# MCU.net
KiCad netlist of a schematic drawn in Altium Designer
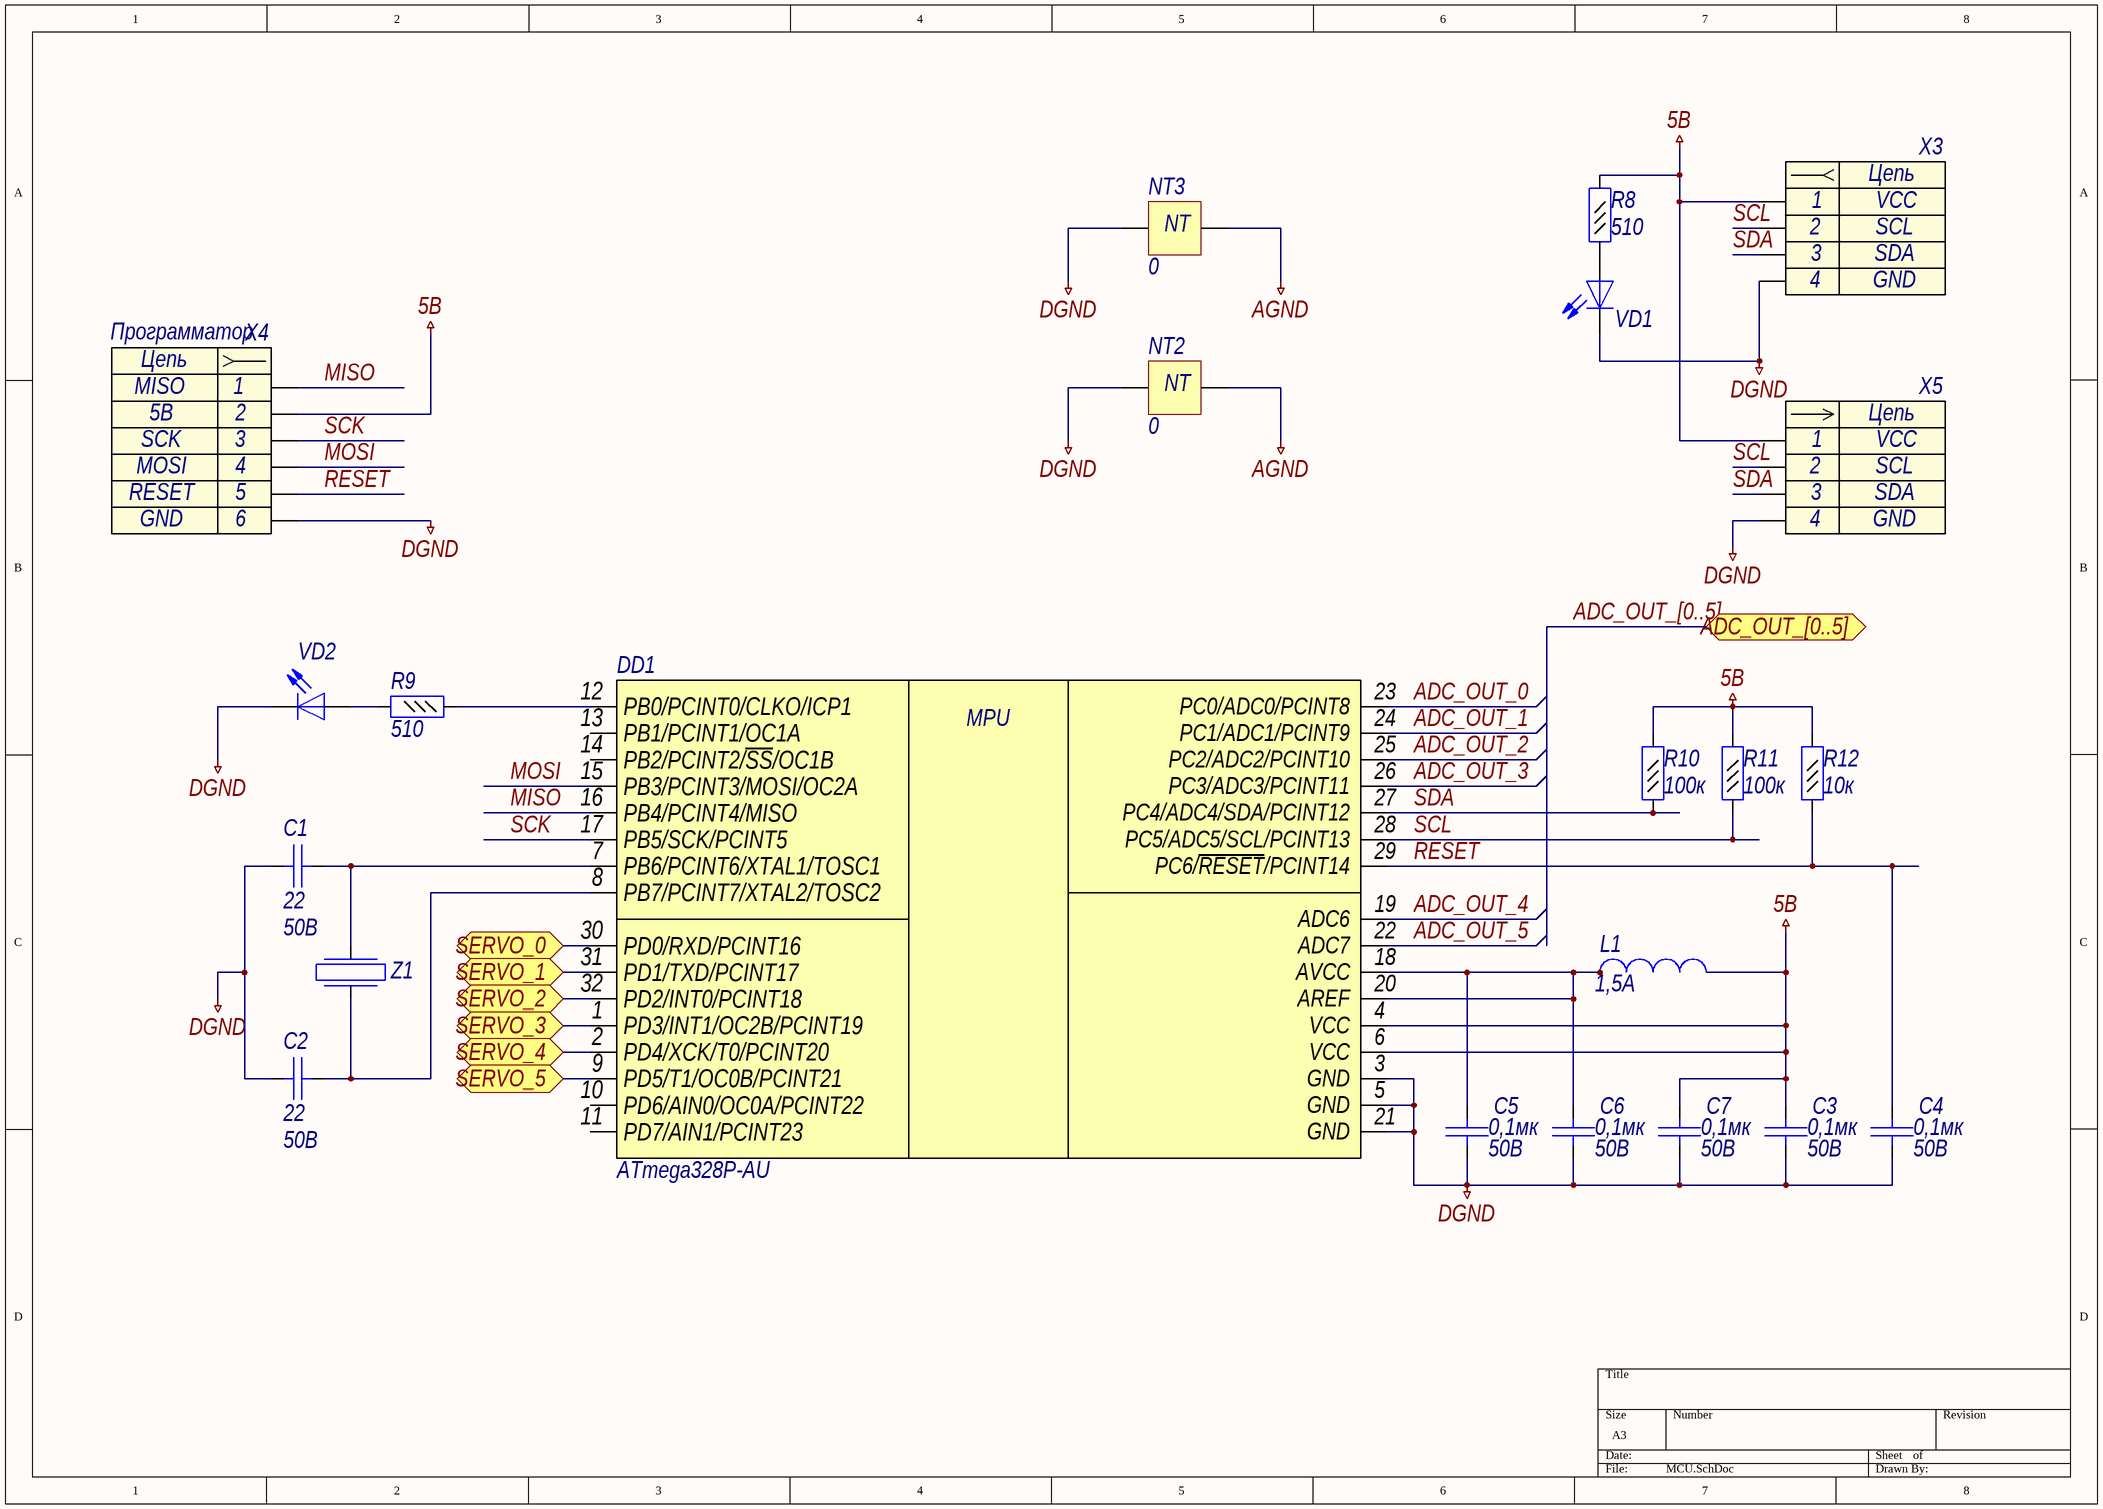
[diagram p0: MCU.SchDoc]

(export (version "E")
  (design (tool "Eeschema 10.0.6"))
  (components
    (comp (ref "C1")
      (value "22")
      (footprint "C0603")
      (description "Конденсатор")
      (fields (field (name "VOLTAGE") "50B") (field (name "PART NUMBER") "CC0603JRNPO9BN220"))
      (libsource (lib "MOP44") (part "Capacitor"))
    )
    (comp (ref "C2")
      (value "22")
      (footprint "C0603")
      (description "Конденсатор")
      (fields (field (name "VOLTAGE") "50B") (field (name "PART NUMBER") "CC0603JRNPO9BN220"))
      (libsource (lib "MOP44") (part "Capacitor"))
    )
    (comp (ref "C3")
      (value "0,1мк")
      (footprint "C0603")
      (description "Конденсатор")
      (fields (field (name "VOLTAGE") "50B") (field (name "PART NUMBER") "GRM188R71H104KA93D"))
      (libsource (lib "MOP44") (part "Capacitor"))
    )
    (comp (ref "C4")
      (value "0,1мк")
      (footprint "C0603")
      (description "Конденсатор")
      (fields (field (name "VOLTAGE") "50B") (field (name "PART NUMBER") "GRM188R71H104KA93D"))
      (libsource (lib "MOP44") (part "Capacitor"))
    )
    (comp (ref "C5")
      (value "0,1мк")
      (footprint "C0603")
      (description "Конденсатор")
      (fields (field (name "VOLTAGE") "50B") (field (name "PART NUMBER") "GRM188R71H104KA93D"))
      (libsource (lib "MOP44") (part "Capacitor"))
    )
    (comp (ref "C6")
      (value "0,1мк")
      (footprint "C0603")
      (description "Конденсатор")
      (fields (field (name "VOLTAGE") "50B") (field (name "PART NUMBER") "GRM188R71H104KA93D"))
      (libsource (lib "MOP44") (part "Capacitor"))
    )
    (comp (ref "C7")
      (value "0,1мк")
      (footprint "C0603")
      (description "Конденсатор")
      (fields (field (name "VOLTAGE") "50B") (field (name "PART NUMBER") "GRM188R71H104KA93D"))
      (libsource (lib "MOP44") (part "Capacitor"))
    )
    (comp (ref "DD1")
      (value "ATmega328P-AU")
      (footprint "TQFP-32")
      (description "Микроконтроллер 8-Бит, picoPower, AVR, 20МГц, 32КБ Flash")
      (fields (field (name "PART NUMBER") "ATmega328P-AU"))
      (libsource (lib "MOP44") (part "ATmega328P-AU"))
    )
    (comp (ref "L1")
      (value "Inductor")
      (footprint "L0603")
      (description "EMI Suppression Filter")
      (fields (field (name "RATED CURRENT") "1,5A") (field (name "PART NUMBER") "BLM18PG181SN1D"))
      (libsource (lib "MOP44") (part "Inductor"))
    )
    (comp (ref "NT2")
      (value "0")
      (footprint "Pofigistor0603")
      (fields (field (name "Comment") "Pofigistor"))
      (libsource (lib "MOP44") (part "Pofigistor"))
    )
    (comp (ref "NT3")
      (value "0")
      (footprint "Pofigistor0603")
      (fields (field (name "Comment") "Pofigistor"))
      (libsource (lib "MOP44") (part "Pofigistor"))
    )
    (comp (ref "R8")
      (value "510")
      (footprint "R0603")
      (description "Резистор")
      (fields (field (name "PART NUMBER") "RC0603FR-07510RL") (field (name "POWER") "0,062Вт"))
      (libsource (lib "") (part "Resistor_0,062Вт_1"))
    )
    (comp (ref "R9")
      (value "510")
      (footprint "R0603")
      (description "Резистор")
      (fields (field (name "PART NUMBER") "RC0603FR-07510RL") (field (name "POWER") "0,062Вт"))
      (libsource (lib "MOP44") (part "Resistor_0,062Вт"))
    )
    (comp (ref "R10")
      (value "100к")
      (footprint "R0603")
      (description "Резистор")
      (fields (field (name "PART NUMBER") "RC0603FR-07100KL") (field (name "POWER") "0,062Вт"))
      (libsource (lib "") (part "Resistor_0,062Вт_1"))
    )
    (comp (ref "R11")
      (value "100к")
      (footprint "R0603")
      (description "Резистор")
      (fields (field (name "PART NUMBER") "RC0603FR-07100KL") (field (name "POWER") "0,062Вт"))
      (libsource (lib "") (part "Resistor_0,062Вт_1"))
    )
    (comp (ref "R12")
      (value "10к")
      (footprint "R0603")
      (description "Резистор")
      (fields (field (name "PART NUMBER") "RC0603FR-0710KL") (field (name "POWER") "0,062Вт"))
      (libsource (lib "") (part "Resistor_0,062Вт_1"))
    )
    (comp (ref "VD1")
      (value "LED")
      (footprint "L_0805")
      (description "Светодиод")
      (fields (field (name "PART NUMBER") "KP-2012EC"))
      (libsource (lib "MOP44") (part "LED"))
    )
    (comp (ref "VD2")
      (value "LED")
      (footprint "L_0805")
      (description "Светодиод")
      (fields (field (name "PART NUMBER") "KP-2012EC"))
      (libsource (lib "MOP44") (part "LED"))
    )
    (comp (ref "X3")
      (value "Header_4_sct")
      (footprint "RJ11_4P4C_V")
      (description "Разъем - 4 конт. розетка")
      (libsource (lib "MOP44") (part "Header_4_sct"))
    )
    (comp (ref "X4")
      (value "Программатор")
      (footprint "PLS2-6")
      (description "Разъем - 6 конт. розетка")
      (libsource (lib "MOP44") (part "Header_6_sct"))
    )
    (comp (ref "X5")
      (value "Header_4_plg")
      (footprint "PLS-4")
      (description "Разъем - 4 конт. вилка")
      (fields (field (name "PART NUMBER") "DS1021-1*4SF112-B"))
      (libsource (lib "MOP44") (part "Header_4_plg"))
    )
    (comp (ref "Z1")
      (value "Crystal")
      (footprint "HC-49SM")
      (description "Кварцевый резонатор")
      (fields (field (name "PART NUMBER") "16.000MHzHC-49SM"))
      (libsource (lib "MOP44") (part "Crystal"))
    )
  )
  (nets
    (net (code "1") (name "/ADC_OUT_0") (class "Default")
      (node (ref "DD1") (pin "23") (pinfunction "PC0/ADC0/PCINT8_23") (pintype "passive"))
    )
    (net (code "2") (name "/ADC_OUT_1") (class "Default")
      (node (ref "DD1") (pin "24") (pinfunction "PC1/ADC1/PCINT9_24") (pintype "passive"))
    )
    (net (code "3") (name "/ADC_OUT_2") (class "Default")
      (node (ref "DD1") (pin "25") (pinfunction "PC2/ADC2/PCINT10_25") (pintype "passive"))
    )
    (net (code "4") (name "/ADC_OUT_3") (class "Default")
      (node (ref "DD1") (pin "26") (pinfunction "PC3/ADC3/PCINT11_26") (pintype "passive"))
    )
    (net (code "5") (name "/ADC_OUT_4") (class "Default")
      (node (ref "DD1") (pin "19") (pinfunction "ADC6_19") (pintype "passive"))
    )
    (net (code "6") (name "/ADC_OUT_5") (class "Default")
      (node (ref "DD1") (pin "22") (pinfunction "ADC7_22") (pintype "passive"))
    )
    (net (code "8") (name "/MISO") (class "Default")
      (node (ref "DD1") (pin "16") (pinfunction "PB4/PCINT4/MISO_16") (pintype "passive"))
      (node (ref "X4") (pin "1") (pinfunction "1_1") (pintype "passive"))
    )
    (net (code "9") (name "/MOSI") (class "Default")
      (node (ref "DD1") (pin "15") (pinfunction "PB3/PCINT3/MOSI/OC2A_15") (pintype "passive"))
      (node (ref "X4") (pin "4") (pinfunction "4_4") (pintype "passive"))
    )
    (net (code "10") (name "/RESET") (class "Default")
      (node (ref "C4") (pin "2") (pinfunction "2_2") (pintype "passive"))
      (node (ref "DD1") (pin "29") (pinfunction "PC6/~{RESET}/PCINT14_29") (pintype "passive"))
      (node (ref "R12") (pin "1") (pinfunction "1_1") (pintype "passive"))
      (node (ref "X4") (pin "5") (pinfunction "5_5") (pintype "passive"))
    )
    (net (code "11") (name "/SCK") (class "Default")
      (node (ref "DD1") (pin "17") (pinfunction "PB5/SCK/PCINT5_17") (pintype "passive"))
      (node (ref "X4") (pin "3") (pinfunction "3_3") (pintype "passive"))
    )
    (net (code "12") (name "/SCL") (class "Default")
      (node (ref "DD1") (pin "28") (pinfunction "PC5/ADC5/SCL/PCINT13_28") (pintype "passive"))
      (node (ref "R11") (pin "1") (pinfunction "1_1") (pintype "passive"))
      (node (ref "X3") (pin "2") (pinfunction "2_2") (pintype "passive"))
      (node (ref "X5") (pin "2") (pinfunction "2_2") (pintype "passive"))
    )
    (net (code "13") (name "/SDA") (class "Default")
      (node (ref "DD1") (pin "27") (pinfunction "PC4/ADC4/SDA/PCINT12_27") (pintype "passive"))
      (node (ref "R10") (pin "1") (pinfunction "1_1") (pintype "passive"))
      (node (ref "X3") (pin "3") (pinfunction "3_3") (pintype "passive"))
      (node (ref "X5") (pin "3") (pinfunction "3_3") (pintype "passive"))
    )
    (net (code "14") (name "/SERVO_0") (class "Default")
      (node (ref "DD1") (pin "30") (pinfunction "PD0/RXD/PCINT16_30") (pintype "passive"))
    )
    (net (code "15") (name "/SERVO_1") (class "Default")
      (node (ref "DD1") (pin "31") (pinfunction "PD1/TXD/PCINT17_31") (pintype "passive"))
    )
    (net (code "16") (name "/SERVO_2") (class "Default")
      (node (ref "DD1") (pin "32") (pinfunction "PD2/INT0/PCINT18_32") (pintype "passive"))
    )
    (net (code "17") (name "/SERVO_3") (class "Default")
      (node (ref "DD1") (pin "1") (pinfunction "PD3/INT1/OC2B/PCINT19_1") (pintype "passive"))
    )
    (net (code "18") (name "/SERVO_4") (class "Default")
      (node (ref "DD1") (pin "2") (pinfunction "PD4/XCK/T0/PCINT20_2") (pintype "passive"))
    )
    (net (code "19") (name "/SERVO_5") (class "Default")
      (node (ref "DD1") (pin "9") (pinfunction "PD5/T1/OC0B/PCINT21_9") (pintype "passive"))
    )
    (net (code "20") (name "5В") (class "Default")
      (node (ref "C3") (pin "2") (pinfunction "2_2") (pintype "passive"))
      (node (ref "C7") (pin "2") (pinfunction "2_2") (pintype "passive"))
      (node (ref "DD1") (pin "4") (pinfunction "VCC_4") (pintype "passive"))
      (node (ref "DD1") (pin "6") (pinfunction "VCC_6") (pintype "passive"))
      (node (ref "L1") (pin "2") (pinfunction "2_2") (pintype "passive"))
      (node (ref "R10") (pin "2") (pinfunction "2_2") (pintype "passive"))
      (node (ref "R11") (pin "2") (pinfunction "2_2") (pintype "passive"))
      (node (ref "R12") (pin "2") (pinfunction "2_2") (pintype "passive"))
      (node (ref "R8") (pin "2") (pinfunction "2_2") (pintype "passive"))
      (node (ref "X3") (pin "1") (pinfunction "1_1") (pintype "passive"))
      (node (ref "X4") (pin "2") (pinfunction "2_2") (pintype "passive"))
      (node (ref "X5") (pin "1") (pinfunction "1_1") (pintype "passive"))
    )
    (net (code "21") (name "AGND") (class "Default")
      (node (ref "NT2") (pin "2") (pinfunction "2_2") (pintype "passive"))
      (node (ref "NT3") (pin "2") (pinfunction "2_2") (pintype "passive"))
    )
    (net (code "22") (name "DGND") (class "Default")
      (node (ref "C1") (pin "1") (pinfunction "1_1") (pintype "passive"))
      (node (ref "C2") (pin "1") (pinfunction "1_1") (pintype "passive"))
      (node (ref "C3") (pin "1") (pinfunction "1_1") (pintype "passive"))
      (node (ref "C4") (pin "1") (pinfunction "1_1") (pintype "passive"))
      (node (ref "C5") (pin "1") (pinfunction "1_1") (pintype "passive"))
      (node (ref "C6") (pin "1") (pinfunction "1_1") (pintype "passive"))
      (node (ref "C7") (pin "1") (pinfunction "1_1") (pintype "passive"))
      (node (ref "DD1") (pin "21") (pinfunction "GND_21") (pintype "passive"))
      (node (ref "DD1") (pin "3") (pinfunction "GND_3") (pintype "passive"))
      (node (ref "DD1") (pin "5") (pinfunction "GND_5") (pintype "passive"))
      (node (ref "NT2") (pin "1") (pinfunction "1_1") (pintype "passive"))
      (node (ref "NT3") (pin "1") (pinfunction "1_1") (pintype "passive"))
      (node (ref "VD1") (pin "1") (pinfunction "K_1") (pintype "passive"))
      (node (ref "VD2") (pin "1") (pinfunction "K_1") (pintype "passive"))
      (node (ref "X3") (pin "4") (pinfunction "4_4") (pintype "passive"))
      (node (ref "X4") (pin "6") (pinfunction "6_6") (pintype "passive"))
      (node (ref "X5") (pin "4") (pinfunction "4_4") (pintype "passive"))
    )
    (net (code "23") (name "Net-(DD1-AREF)") (class "Default")
      (node (ref "C5") (pin "2") (pinfunction "2_2") (pintype "passive"))
      (node (ref "C6") (pin "2") (pinfunction "2_2") (pintype "passive"))
      (node (ref "DD1") (pin "18") (pinfunction "AVCC_18") (pintype "passive"))
      (node (ref "DD1") (pin "20") (pinfunction "AREF_20") (pintype "passive"))
      (node (ref "L1") (pin "1") (pinfunction "1_1") (pintype "passive"))
    )
    (net (code "24") (name "Net-(DD1-PB0{slash}PCINT0{slash}CLKO{slash}ICP1)") (class "Default")
      (node (ref "DD1") (pin "12") (pinfunction "PB0/PCINT0/CLKO/ICP1_12") (pintype "passive"))
      (node (ref "R9") (pin "1") (pinfunction "1_1") (pintype "passive"))
    )
    (net (code "25") (name "Net-(DD1-PB6{slash}PCINT6{slash}XTAL1{slash}TOSC1)") (class "Default")
      (node (ref "C1") (pin "2") (pinfunction "2_2") (pintype "passive"))
      (node (ref "DD1") (pin "7") (pinfunction "PB6/PCINT6/XTAL1/TOSC1_7") (pintype "passive"))
      (node (ref "Z1") (pin "2") (pinfunction "2_2") (pintype "passive"))
    )
    (net (code "26") (name "Net-(DD1-PB7{slash}PCINT7{slash}XTAL2{slash}TOSC2)") (class "Default")
      (node (ref "C2") (pin "2") (pinfunction "2_2") (pintype "passive"))
      (node (ref "DD1") (pin "8") (pinfunction "PB7/PCINT7/XTAL2/TOSC2_8") (pintype "passive"))
      (node (ref "Z1") (pin "1") (pinfunction "1_1") (pintype "passive"))
    )
    (net (code "27") (name "Net-(VD1-A)") (class "Default")
      (node (ref "R8") (pin "1") (pinfunction "1_1") (pintype "passive"))
      (node (ref "VD1") (pin "2") (pinfunction "A_2") (pintype "passive"))
    )
    (net (code "28") (name "Net-(VD2-A)") (class "Default")
      (node (ref "R9") (pin "2") (pinfunction "2_2") (pintype "passive"))
      (node (ref "VD2") (pin "2") (pinfunction "A_2") (pintype "passive"))
    )
    (net (code "29") (name "unconnected-(DD1-PB1{slash}PCINT1{slash}OC1A-Pad13)") (class "Default")
      (node (ref "DD1") (pin "13") (pinfunction "PB1/PCINT1/OC1A_13") (pintype "passive"))
    )
    (net (code "30") (name "unconnected-(DD1-PB2{slash}PCINT2{slash}~{SS}{slash}OC1B-Pad14)") (class "Default")
      (node (ref "DD1") (pin "14") (pinfunction "PB2/PCINT2/~{SS}/OC1B_14") (pintype "passive"))
    )
    (net (code "31") (name "unconnected-(DD1-PD6{slash}AIN0{slash}OC0A{slash}PCINT22-Pad10)") (class "Default")
      (node (ref "DD1") (pin "10") (pinfunction "PD6/AIN0/OC0A/PCINT22_10") (pintype "passive"))
    )
    (net (code "32") (name "unconnected-(DD1-PD7{slash}AIN1{slash}PCINT23-Pad11)") (class "Default")
      (node (ref "DD1") (pin "11") (pinfunction "PD7/AIN1/PCINT23_11") (pintype "passive"))
    )
  )
)
